# BUF_BUS_TEE_1.net
KiCad netlist of a schematic drawn in EAGLE
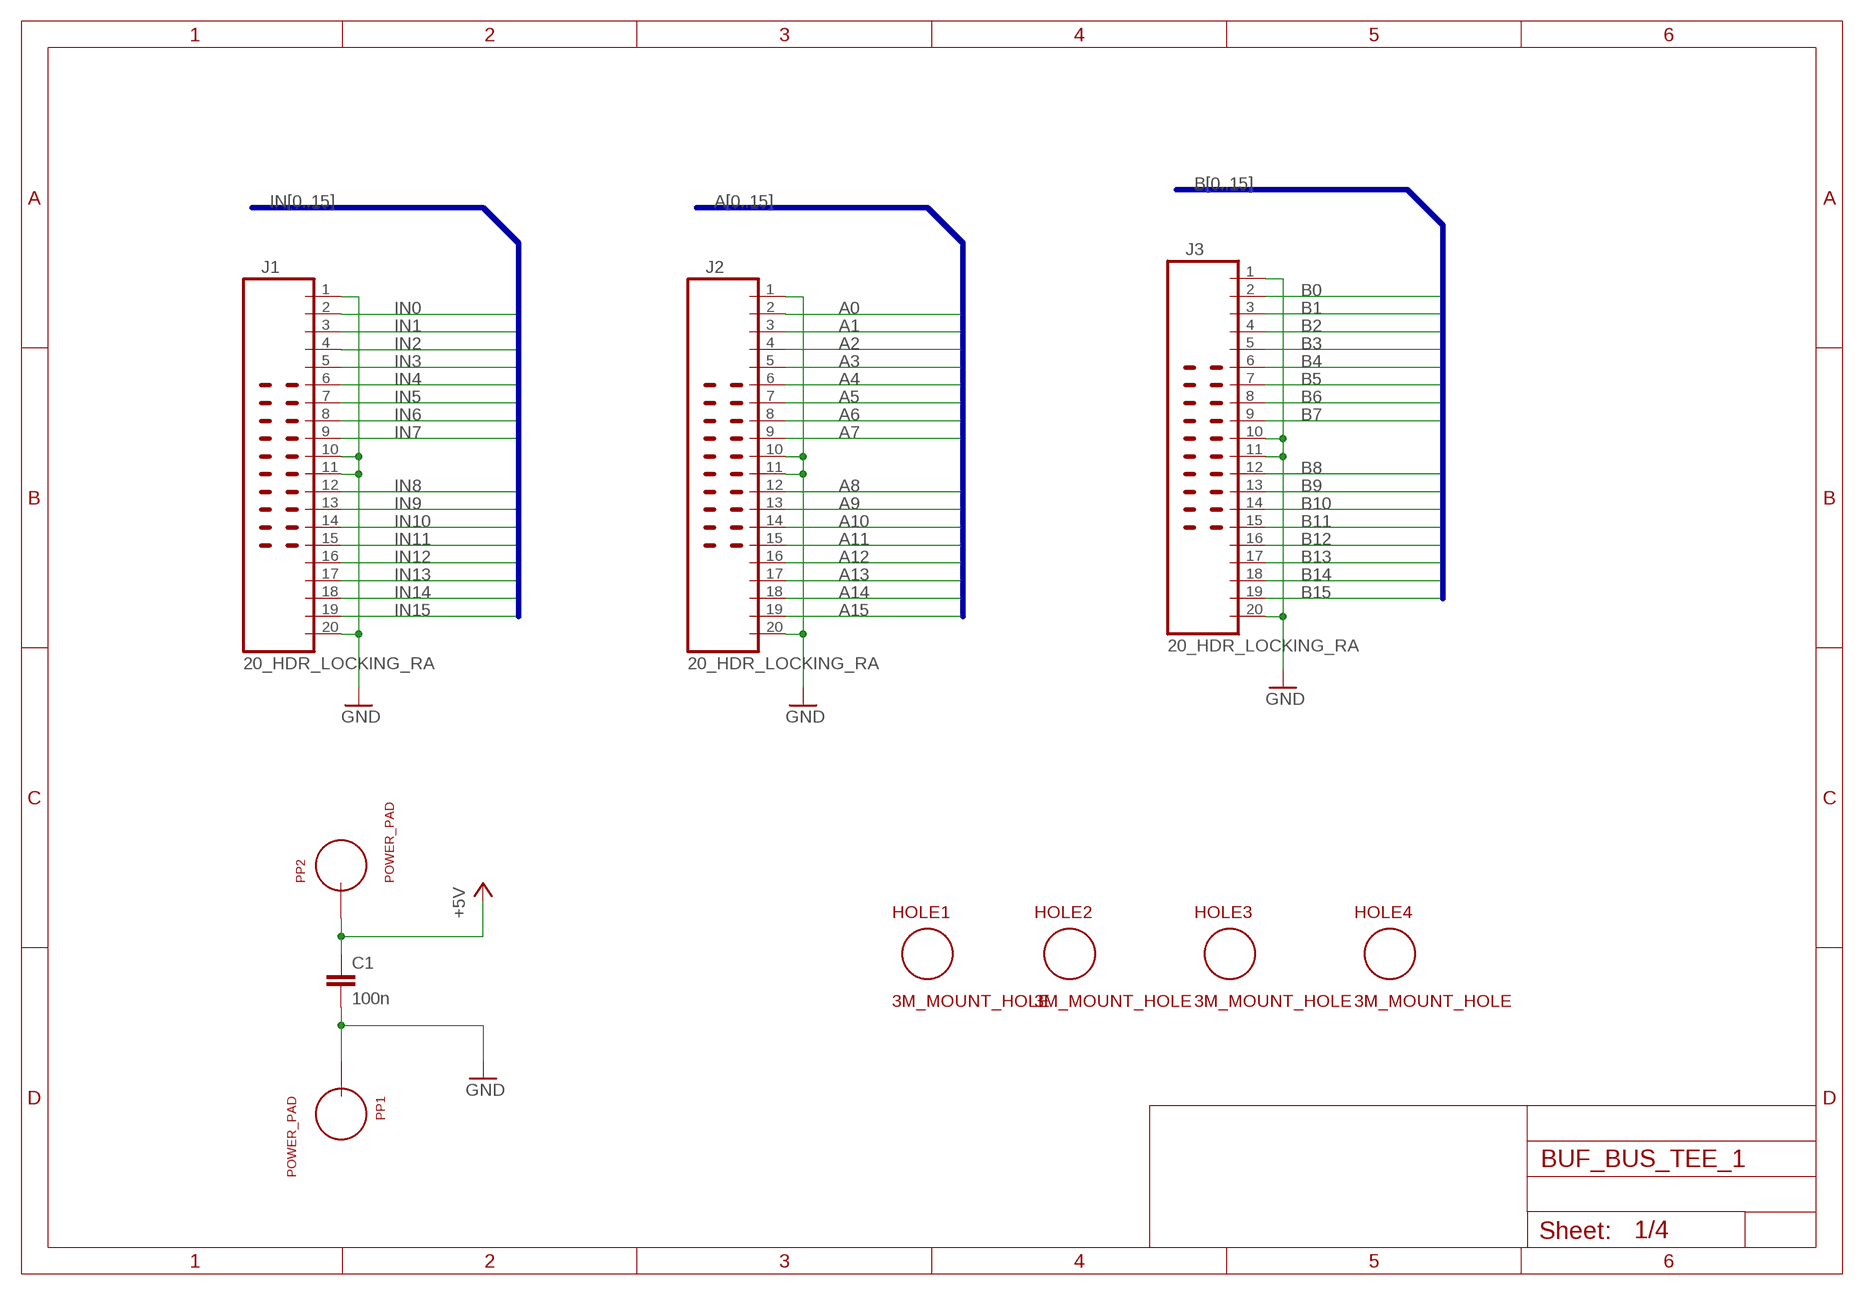
[diagram p0: schematic, sheet 1]
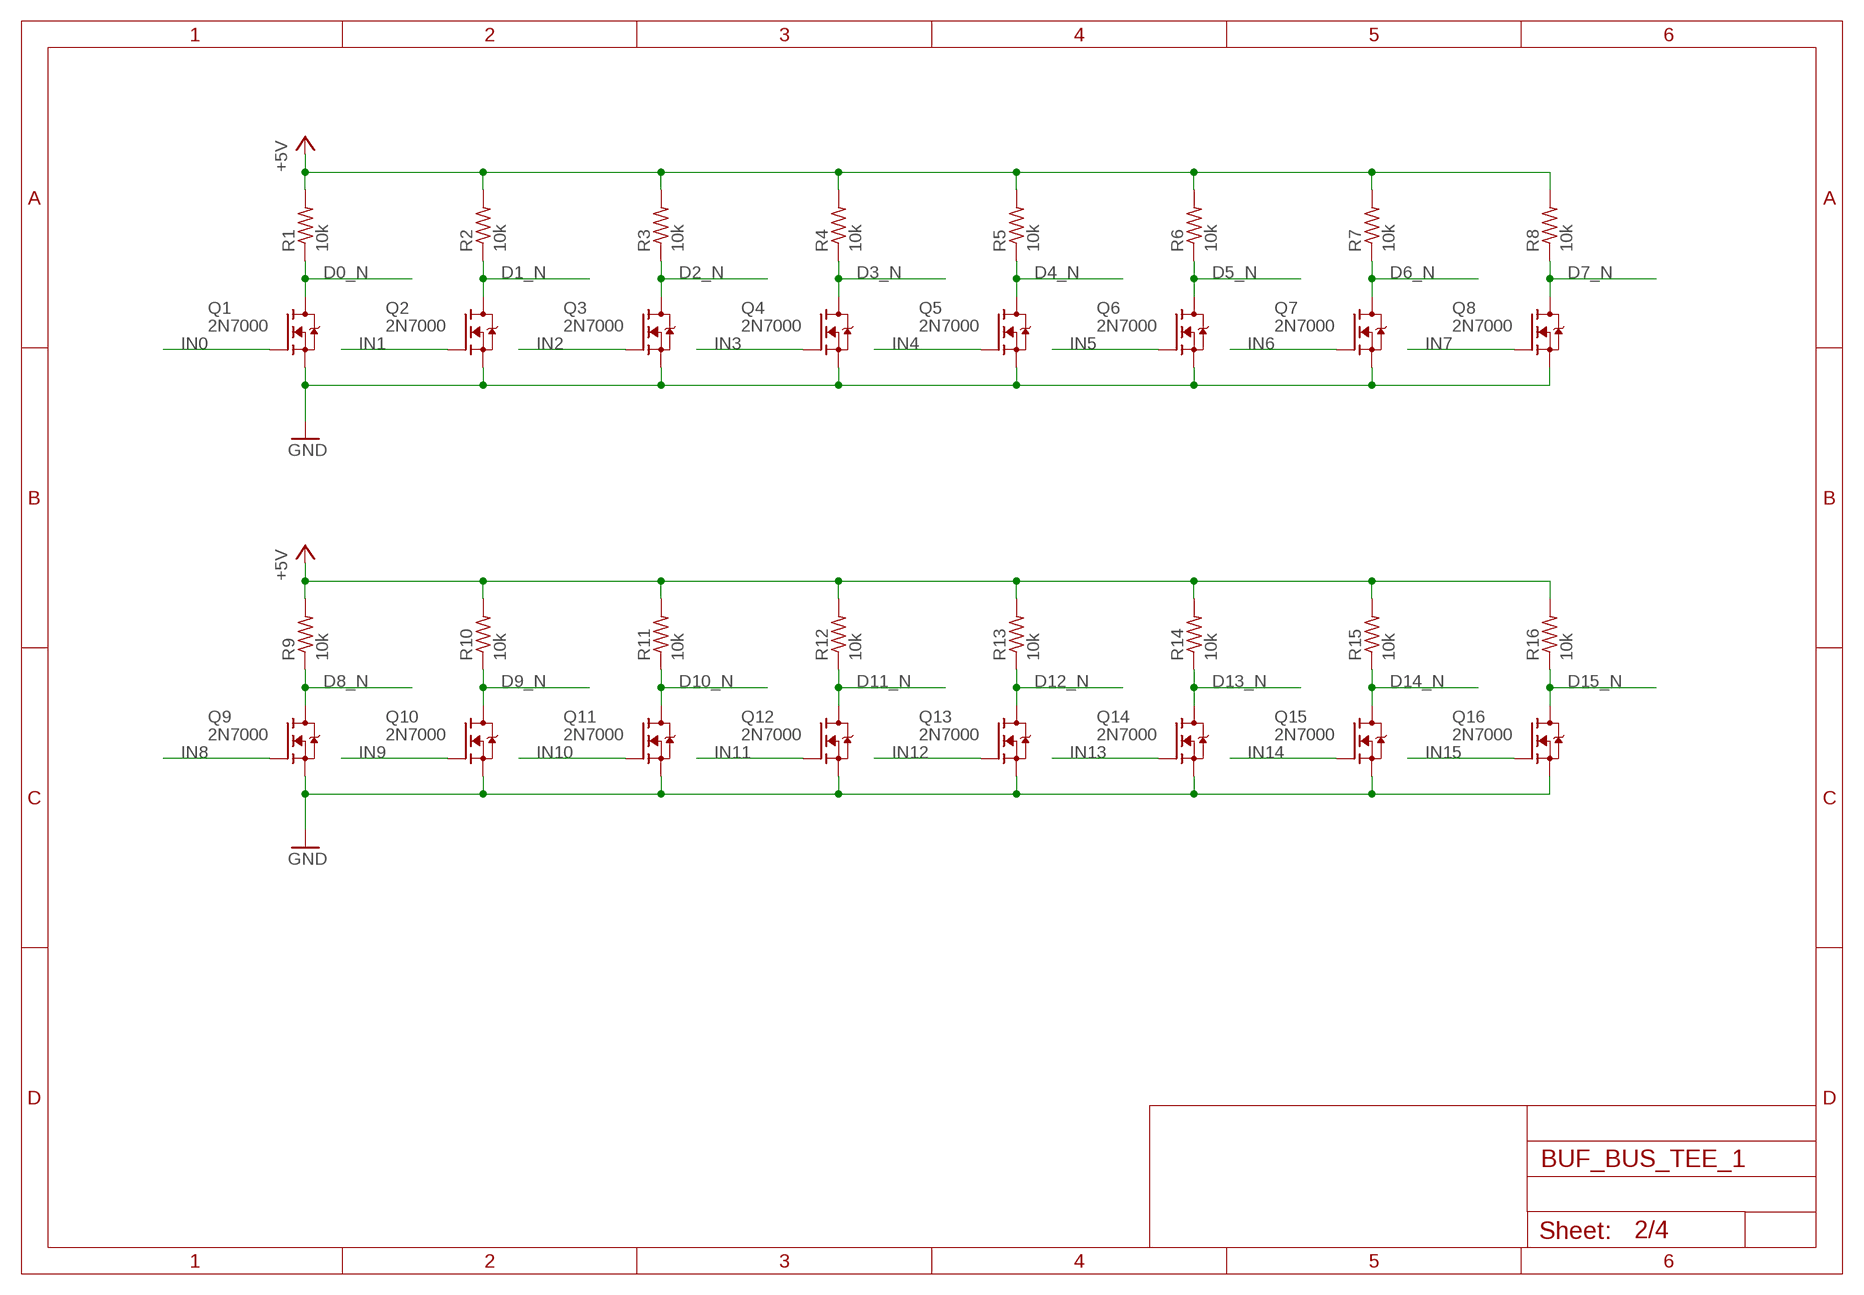
[diagram p1: schematic, sheet 2]
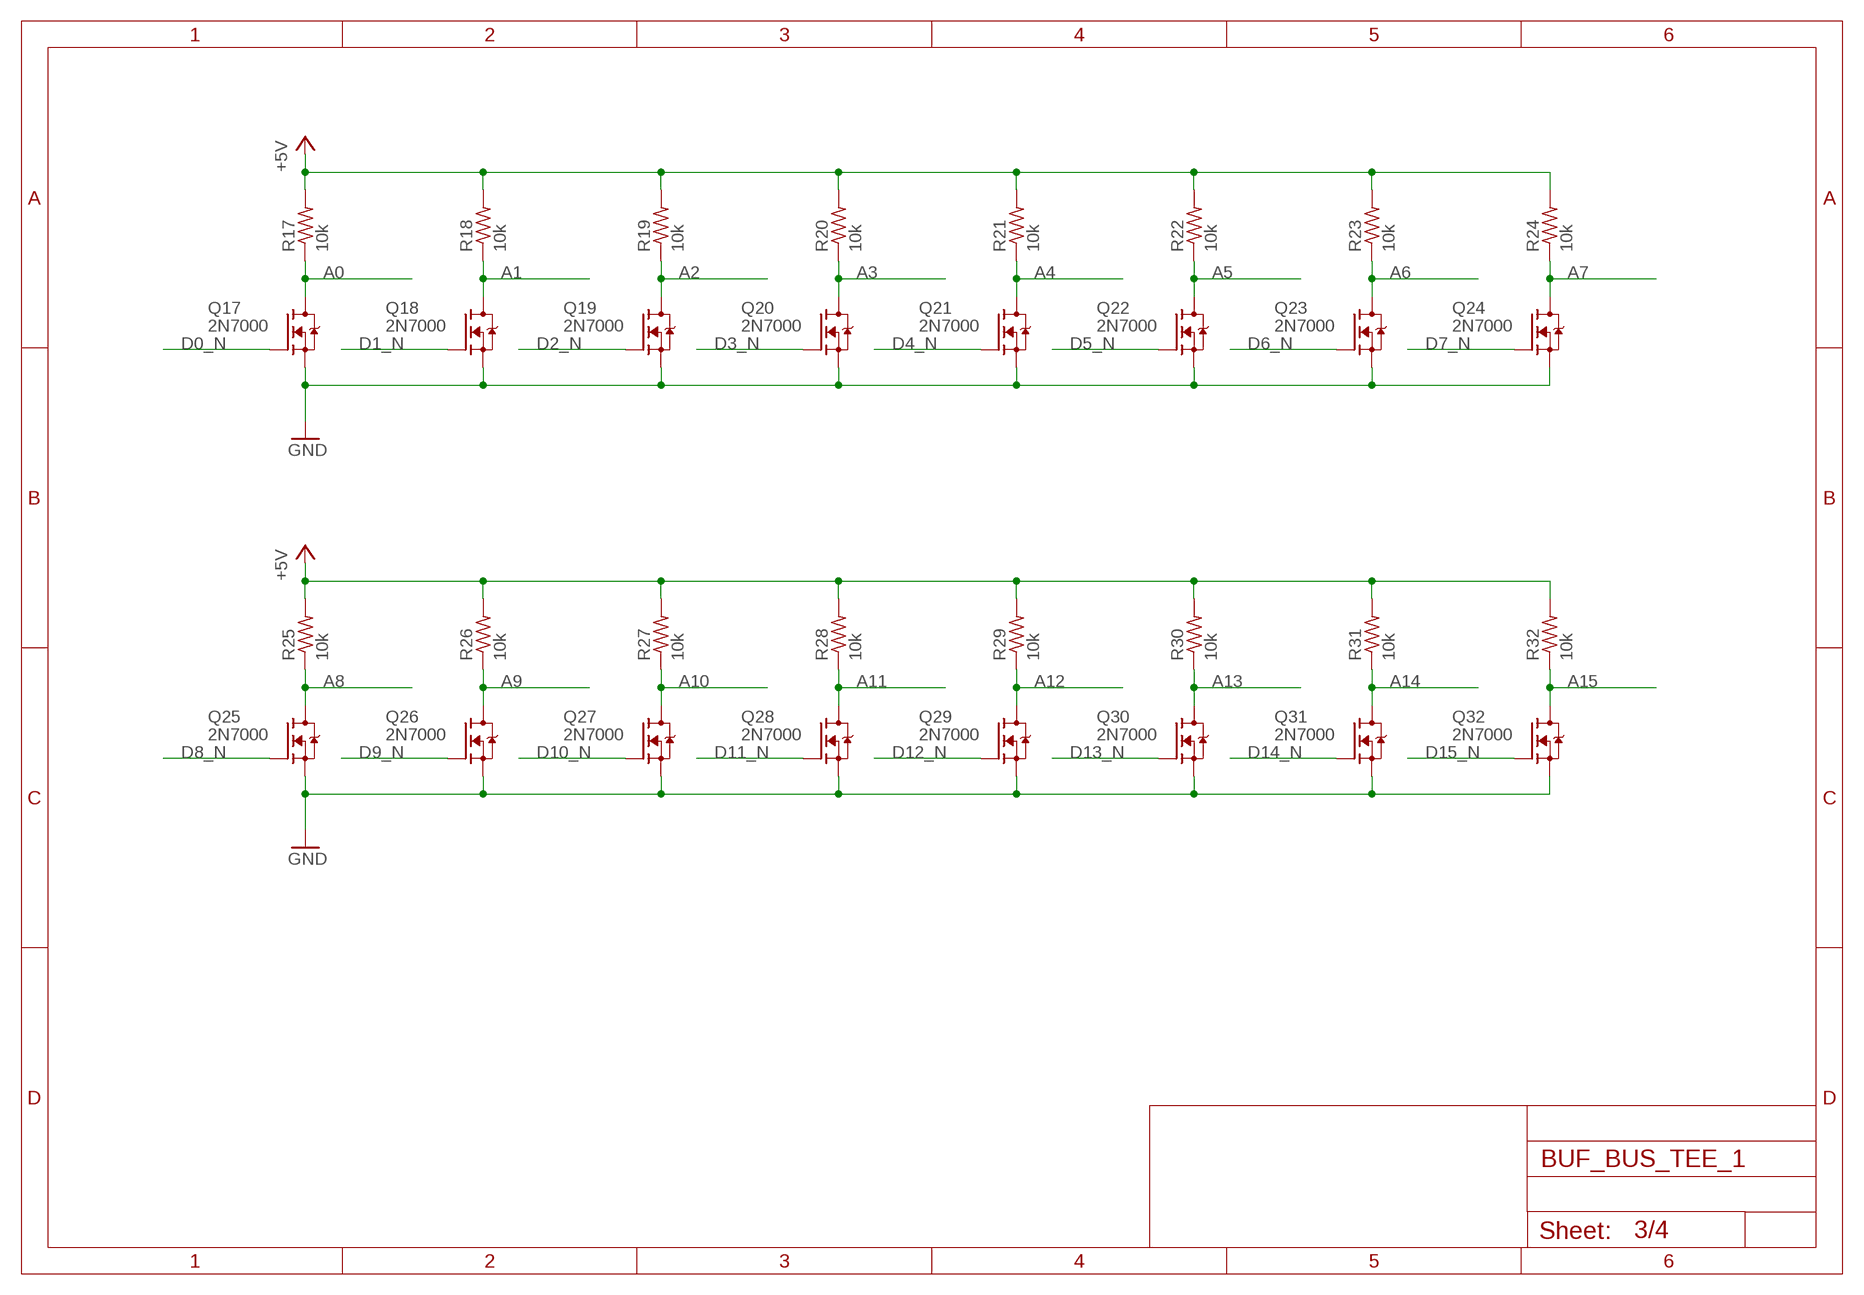
[diagram p2: schematic, sheet 3]
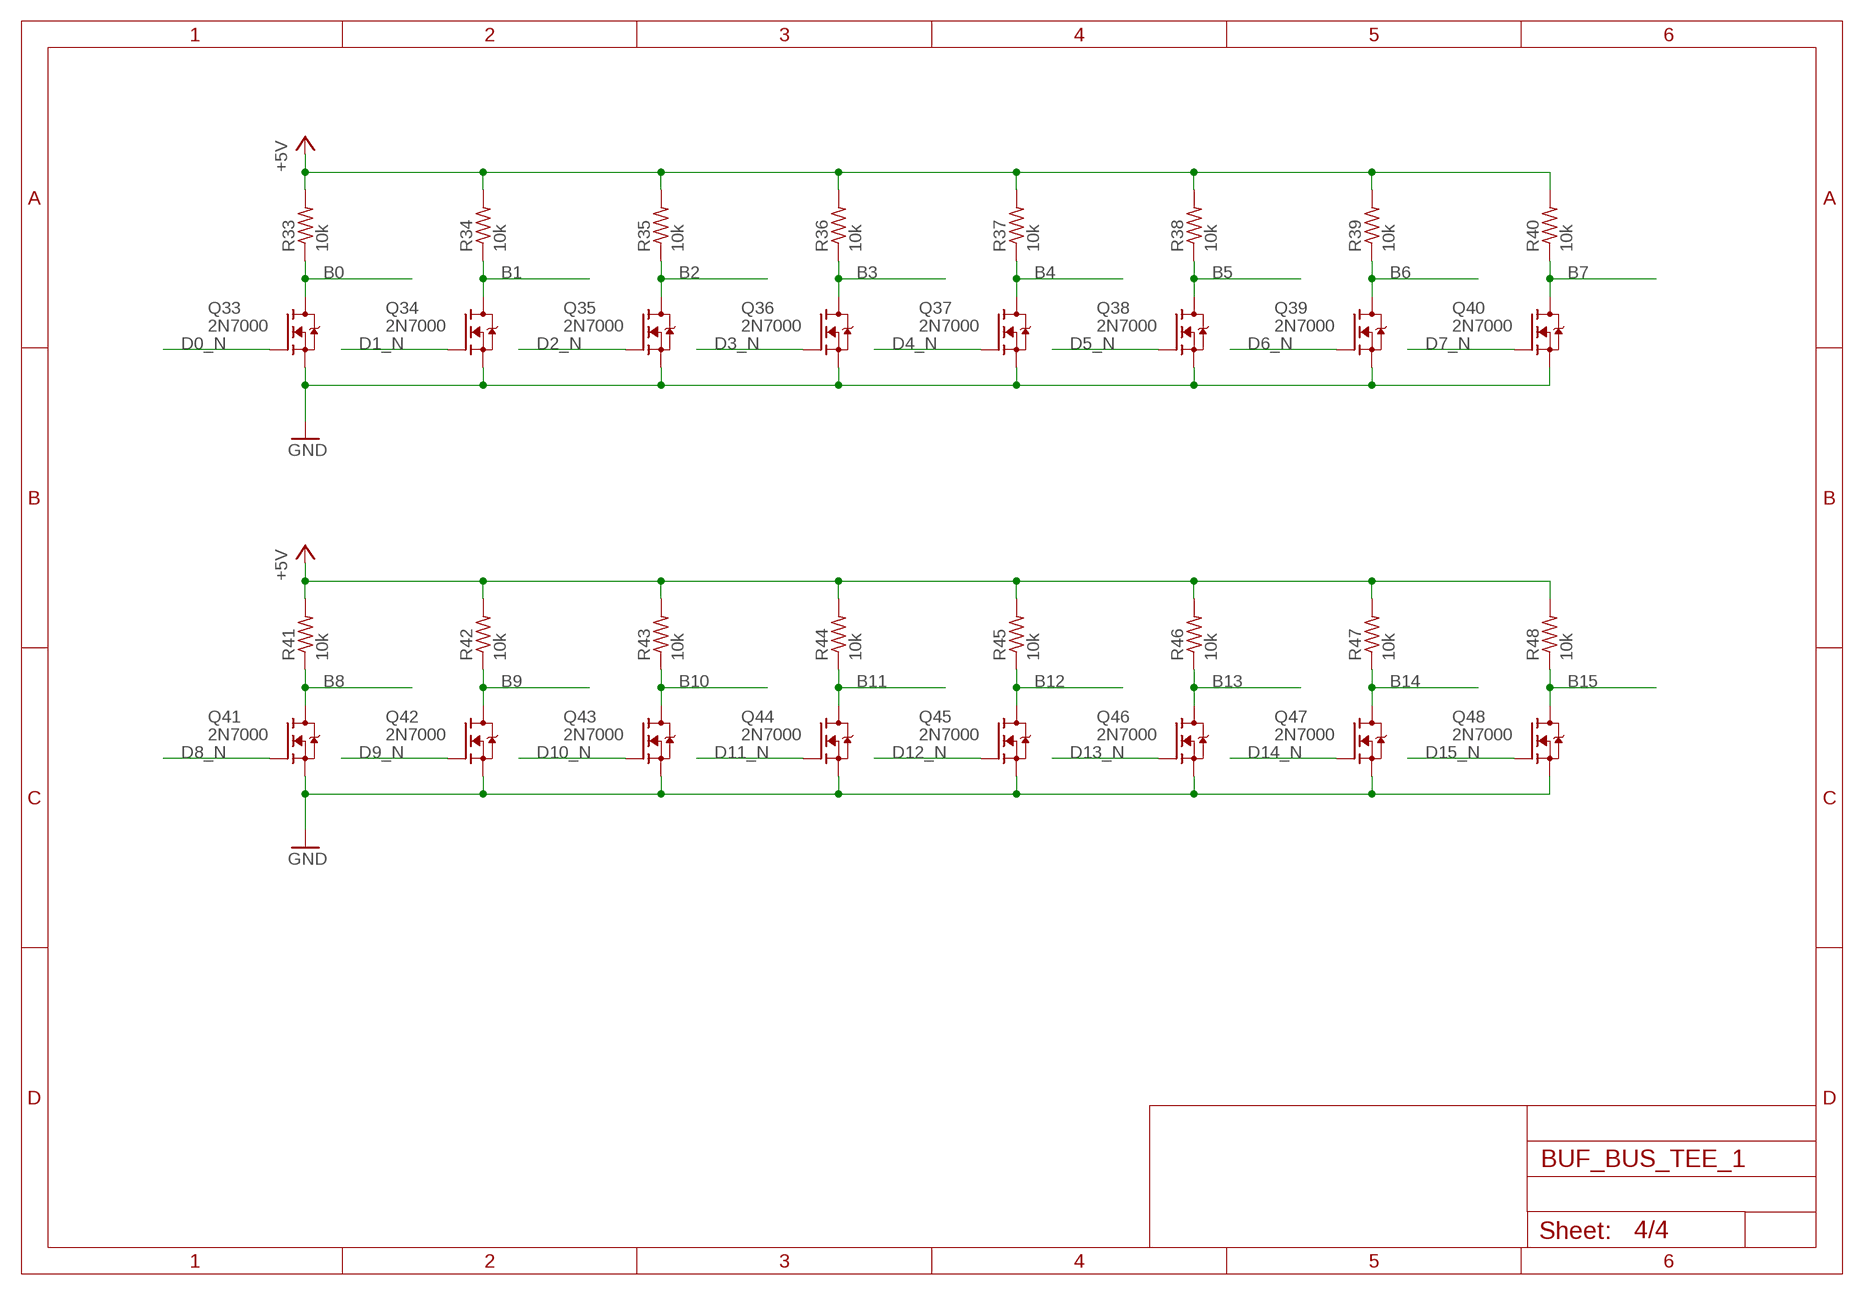
[diagram p3: schematic, sheet 4]

(export (version "E")
  (design (tool "Eeschema 10.0.6"))
  (components
    (comp (ref "Q1")
      (value "2N7000")
      (footprint "eagle-import:TO92-DGS")
      (libsource (lib "eagle-import") (part "2N7000"))
    )
    (comp (ref "Q2")
      (value "2N7000")
      (footprint "eagle-import:TO92-DGS")
      (libsource (lib "eagle-import") (part "2N7000"))
    )
    (comp (ref "Q3")
      (value "2N7000")
      (footprint "eagle-import:TO92-DGS")
      (libsource (lib "eagle-import") (part "2N7000"))
    )
    (comp (ref "Q4")
      (value "2N7000")
      (footprint "eagle-import:TO92-DGS")
      (libsource (lib "eagle-import") (part "2N7000"))
    )
    (comp (ref "Q5")
      (value "2N7000")
      (footprint "eagle-import:TO92-DGS")
      (libsource (lib "eagle-import") (part "2N7000"))
    )
    (comp (ref "Q6")
      (value "2N7000")
      (footprint "eagle-import:TO92-DGS")
      (libsource (lib "eagle-import") (part "2N7000"))
    )
    (comp (ref "Q7")
      (value "2N7000")
      (footprint "eagle-import:TO92-DGS")
      (libsource (lib "eagle-import") (part "2N7000"))
    )
    (comp (ref "Q8")
      (value "2N7000")
      (footprint "eagle-import:TO92-DGS")
      (libsource (lib "eagle-import") (part "2N7000"))
    )
    (comp (ref "Q9")
      (value "2N7000")
      (footprint "eagle-import:TO92-DGS")
      (libsource (lib "eagle-import") (part "2N7000"))
    )
    (comp (ref "Q10")
      (value "2N7000")
      (footprint "eagle-import:TO92-DGS")
      (libsource (lib "eagle-import") (part "2N7000"))
    )
    (comp (ref "Q11")
      (value "2N7000")
      (footprint "eagle-import:TO92-DGS")
      (libsource (lib "eagle-import") (part "2N7000"))
    )
    (comp (ref "Q12")
      (value "2N7000")
      (footprint "eagle-import:TO92-DGS")
      (libsource (lib "eagle-import") (part "2N7000"))
    )
    (comp (ref "Q13")
      (value "2N7000")
      (footprint "eagle-import:TO92-DGS")
      (libsource (lib "eagle-import") (part "2N7000"))
    )
    (comp (ref "Q14")
      (value "2N7000")
      (footprint "eagle-import:TO92-DGS")
      (libsource (lib "eagle-import") (part "2N7000"))
    )
    (comp (ref "Q15")
      (value "2N7000")
      (footprint "eagle-import:TO92-DGS")
      (libsource (lib "eagle-import") (part "2N7000"))
    )
    (comp (ref "Q16")
      (value "2N7000")
      (footprint "eagle-import:TO92-DGS")
      (libsource (lib "eagle-import") (part "2N7000"))
    )
    (comp (ref "R1")
      (value "10k")
      (footprint "eagle-import:R_P2INCH")
      (libsource (lib "eagle-import") (part "R_P2INCH"))
    )
    (comp (ref "R2")
      (value "10k")
      (footprint "eagle-import:R_P2INCH")
      (libsource (lib "eagle-import") (part "R_P2INCH"))
    )
    (comp (ref "R3")
      (value "10k")
      (footprint "eagle-import:R_P2INCH")
      (libsource (lib "eagle-import") (part "R_P2INCH"))
    )
    (comp (ref "R4")
      (value "10k")
      (footprint "eagle-import:R_P2INCH")
      (libsource (lib "eagle-import") (part "R_P2INCH"))
    )
    (comp (ref "R5")
      (value "10k")
      (footprint "eagle-import:R_P2INCH")
      (libsource (lib "eagle-import") (part "R_P2INCH"))
    )
    (comp (ref "R6")
      (value "10k")
      (footprint "eagle-import:R_P2INCH")
      (libsource (lib "eagle-import") (part "R_P2INCH"))
    )
    (comp (ref "R7")
      (value "10k")
      (footprint "eagle-import:R_P2INCH")
      (libsource (lib "eagle-import") (part "R_P2INCH"))
    )
    (comp (ref "R8")
      (value "10k")
      (footprint "eagle-import:R_P2INCH")
      (libsource (lib "eagle-import") (part "R_P2INCH"))
    )
    (comp (ref "R9")
      (value "10k")
      (footprint "eagle-import:R_P2INCH")
      (libsource (lib "eagle-import") (part "R_P2INCH"))
    )
    (comp (ref "R10")
      (value "10k")
      (footprint "eagle-import:R_P2INCH")
      (libsource (lib "eagle-import") (part "R_P2INCH"))
    )
    (comp (ref "R11")
      (value "10k")
      (footprint "eagle-import:R_P2INCH")
      (libsource (lib "eagle-import") (part "R_P2INCH"))
    )
    (comp (ref "R12")
      (value "10k")
      (footprint "eagle-import:R_P2INCH")
      (libsource (lib "eagle-import") (part "R_P2INCH"))
    )
    (comp (ref "R13")
      (value "10k")
      (footprint "eagle-import:R_P2INCH")
      (libsource (lib "eagle-import") (part "R_P2INCH"))
    )
    (comp (ref "R14")
      (value "10k")
      (footprint "eagle-import:R_P2INCH")
      (libsource (lib "eagle-import") (part "R_P2INCH"))
    )
    (comp (ref "R15")
      (value "10k")
      (footprint "eagle-import:R_P2INCH")
      (libsource (lib "eagle-import") (part "R_P2INCH"))
    )
    (comp (ref "R16")
      (value "10k")
      (footprint "eagle-import:R_P2INCH")
      (libsource (lib "eagle-import") (part "R_P2INCH"))
    )
    (comp (ref "C1")
      (value "100n")
      (footprint "eagle-import:CAP_P2INCH")
      (libsource (lib "eagle-import") (part "C_P2INCH"))
    )
    (comp (ref "HOLE1")
      (value "3M_MOUNT_HOLE")
      (footprint "eagle-import:3M_HOLE")
      (libsource (lib "eagle-import") (part "3M_MOUNT_HOLE"))
    )
    (comp (ref "HOLE2")
      (value "3M_MOUNT_HOLE")
      (footprint "eagle-import:3M_HOLE")
      (libsource (lib "eagle-import") (part "3M_MOUNT_HOLE"))
    )
    (comp (ref "HOLE3")
      (value "3M_MOUNT_HOLE")
      (footprint "eagle-import:3M_HOLE")
      (libsource (lib "eagle-import") (part "3M_MOUNT_HOLE"))
    )
    (comp (ref "HOLE4")
      (value "3M_MOUNT_HOLE")
      (footprint "eagle-import:3M_HOLE")
      (libsource (lib "eagle-import") (part "3M_MOUNT_HOLE"))
    )
    (comp (ref "J1")
      (value "20_HDR_LOCKING_RA")
      (footprint "eagle-import:20_HDR_LOCKING_RA")
      (libsource (lib "eagle-import") (part "20_HDR_LOCKING_RA"))
    )
    (comp (ref "J2")
      (value "20_HDR_LOCKING_RA")
      (footprint "eagle-import:20_HDR_LOCKING_RA")
      (libsource (lib "eagle-import") (part "20_HDR_LOCKING_RA"))
    )
    (comp (ref "J3")
      (value "20_HDR_LOCKING_RA")
      (footprint "eagle-import:20_HDR_LOCKING_RA")
      (libsource (lib "eagle-import") (part "20_HDR_LOCKING_RA"))
    )
    (comp (ref "PP1")
      (value "POWER_PAD")
      (footprint "eagle-import:POWER_PAD")
      (libsource (lib "eagle-import") (part "POWER_PAD"))
    )
    (comp (ref "PP2")
      (value "POWER_PAD")
      (footprint "eagle-import:POWER_PAD")
      (libsource (lib "eagle-import") (part "POWER_PAD"))
    )
    (comp (ref "Q17")
      (value "2N7000")
      (footprint "eagle-import:TO92-DGS")
      (libsource (lib "eagle-import") (part "2N7000"))
    )
    (comp (ref "Q18")
      (value "2N7000")
      (footprint "eagle-import:TO92-DGS")
      (libsource (lib "eagle-import") (part "2N7000"))
    )
    (comp (ref "Q19")
      (value "2N7000")
      (footprint "eagle-import:TO92-DGS")
      (libsource (lib "eagle-import") (part "2N7000"))
    )
    (comp (ref "Q20")
      (value "2N7000")
      (footprint "eagle-import:TO92-DGS")
      (libsource (lib "eagle-import") (part "2N7000"))
    )
    (comp (ref "Q21")
      (value "2N7000")
      (footprint "eagle-import:TO92-DGS")
      (libsource (lib "eagle-import") (part "2N7000"))
    )
    (comp (ref "Q22")
      (value "2N7000")
      (footprint "eagle-import:TO92-DGS")
      (libsource (lib "eagle-import") (part "2N7000"))
    )
    (comp (ref "Q23")
      (value "2N7000")
      (footprint "eagle-import:TO92-DGS")
      (libsource (lib "eagle-import") (part "2N7000"))
    )
    (comp (ref "Q24")
      (value "2N7000")
      (footprint "eagle-import:TO92-DGS")
      (libsource (lib "eagle-import") (part "2N7000"))
    )
    (comp (ref "Q25")
      (value "2N7000")
      (footprint "eagle-import:TO92-DGS")
      (libsource (lib "eagle-import") (part "2N7000"))
    )
    (comp (ref "Q26")
      (value "2N7000")
      (footprint "eagle-import:TO92-DGS")
      (libsource (lib "eagle-import") (part "2N7000"))
    )
    (comp (ref "Q27")
      (value "2N7000")
      (footprint "eagle-import:TO92-DGS")
      (libsource (lib "eagle-import") (part "2N7000"))
    )
    (comp (ref "Q28")
      (value "2N7000")
      (footprint "eagle-import:TO92-DGS")
      (libsource (lib "eagle-import") (part "2N7000"))
    )
    (comp (ref "Q29")
      (value "2N7000")
      (footprint "eagle-import:TO92-DGS")
      (libsource (lib "eagle-import") (part "2N7000"))
    )
    (comp (ref "Q30")
      (value "2N7000")
      (footprint "eagle-import:TO92-DGS")
      (libsource (lib "eagle-import") (part "2N7000"))
    )
    (comp (ref "Q31")
      (value "2N7000")
      (footprint "eagle-import:TO92-DGS")
      (libsource (lib "eagle-import") (part "2N7000"))
    )
    (comp (ref "Q32")
      (value "2N7000")
      (footprint "eagle-import:TO92-DGS")
      (libsource (lib "eagle-import") (part "2N7000"))
    )
    (comp (ref "R17")
      (value "10k")
      (footprint "eagle-import:R_P2INCH")
      (libsource (lib "eagle-import") (part "R_P2INCH"))
    )
    (comp (ref "R18")
      (value "10k")
      (footprint "eagle-import:R_P2INCH")
      (libsource (lib "eagle-import") (part "R_P2INCH"))
    )
    (comp (ref "R19")
      (value "10k")
      (footprint "eagle-import:R_P2INCH")
      (libsource (lib "eagle-import") (part "R_P2INCH"))
    )
    (comp (ref "R20")
      (value "10k")
      (footprint "eagle-import:R_P2INCH")
      (libsource (lib "eagle-import") (part "R_P2INCH"))
    )
    (comp (ref "R21")
      (value "10k")
      (footprint "eagle-import:R_P2INCH")
      (libsource (lib "eagle-import") (part "R_P2INCH"))
    )
    (comp (ref "R22")
      (value "10k")
      (footprint "eagle-import:R_P2INCH")
      (libsource (lib "eagle-import") (part "R_P2INCH"))
    )
    (comp (ref "R23")
      (value "10k")
      (footprint "eagle-import:R_P2INCH")
      (libsource (lib "eagle-import") (part "R_P2INCH"))
    )
    (comp (ref "R24")
      (value "10k")
      (footprint "eagle-import:R_P2INCH")
      (libsource (lib "eagle-import") (part "R_P2INCH"))
    )
    (comp (ref "R25")
      (value "10k")
      (footprint "eagle-import:R_P2INCH")
      (libsource (lib "eagle-import") (part "R_P2INCH"))
    )
    (comp (ref "R26")
      (value "10k")
      (footprint "eagle-import:R_P2INCH")
      (libsource (lib "eagle-import") (part "R_P2INCH"))
    )
    (comp (ref "R27")
      (value "10k")
      (footprint "eagle-import:R_P2INCH")
      (libsource (lib "eagle-import") (part "R_P2INCH"))
    )
    (comp (ref "R28")
      (value "10k")
      (footprint "eagle-import:R_P2INCH")
      (libsource (lib "eagle-import") (part "R_P2INCH"))
    )
    (comp (ref "R29")
      (value "10k")
      (footprint "eagle-import:R_P2INCH")
      (libsource (lib "eagle-import") (part "R_P2INCH"))
    )
    (comp (ref "R30")
      (value "10k")
      (footprint "eagle-import:R_P2INCH")
      (libsource (lib "eagle-import") (part "R_P2INCH"))
    )
    (comp (ref "R31")
      (value "10k")
      (footprint "eagle-import:R_P2INCH")
      (libsource (lib "eagle-import") (part "R_P2INCH"))
    )
    (comp (ref "R32")
      (value "10k")
      (footprint "eagle-import:R_P2INCH")
      (libsource (lib "eagle-import") (part "R_P2INCH"))
    )
    (comp (ref "Q33")
      (value "2N7000")
      (footprint "eagle-import:TO92-DGS")
      (libsource (lib "eagle-import") (part "2N7000"))
    )
    (comp (ref "Q34")
      (value "2N7000")
      (footprint "eagle-import:TO92-DGS")
      (libsource (lib "eagle-import") (part "2N7000"))
    )
    (comp (ref "Q35")
      (value "2N7000")
      (footprint "eagle-import:TO92-DGS")
      (libsource (lib "eagle-import") (part "2N7000"))
    )
    (comp (ref "Q36")
      (value "2N7000")
      (footprint "eagle-import:TO92-DGS")
      (libsource (lib "eagle-import") (part "2N7000"))
    )
    (comp (ref "Q37")
      (value "2N7000")
      (footprint "eagle-import:TO92-DGS")
      (libsource (lib "eagle-import") (part "2N7000"))
    )
    (comp (ref "Q38")
      (value "2N7000")
      (footprint "eagle-import:TO92-DGS")
      (libsource (lib "eagle-import") (part "2N7000"))
    )
    (comp (ref "Q39")
      (value "2N7000")
      (footprint "eagle-import:TO92-DGS")
      (libsource (lib "eagle-import") (part "2N7000"))
    )
    (comp (ref "Q40")
      (value "2N7000")
      (footprint "eagle-import:TO92-DGS")
      (libsource (lib "eagle-import") (part "2N7000"))
    )
    (comp (ref "Q41")
      (value "2N7000")
      (footprint "eagle-import:TO92-DGS")
      (libsource (lib "eagle-import") (part "2N7000"))
    )
    (comp (ref "Q42")
      (value "2N7000")
      (footprint "eagle-import:TO92-DGS")
      (libsource (lib "eagle-import") (part "2N7000"))
    )
    (comp (ref "Q43")
      (value "2N7000")
      (footprint "eagle-import:TO92-DGS")
      (libsource (lib "eagle-import") (part "2N7000"))
    )
    (comp (ref "Q44")
      (value "2N7000")
      (footprint "eagle-import:TO92-DGS")
      (libsource (lib "eagle-import") (part "2N7000"))
    )
    (comp (ref "Q45")
      (value "2N7000")
      (footprint "eagle-import:TO92-DGS")
      (libsource (lib "eagle-import") (part "2N7000"))
    )
    (comp (ref "Q46")
      (value "2N7000")
      (footprint "eagle-import:TO92-DGS")
      (libsource (lib "eagle-import") (part "2N7000"))
    )
    (comp (ref "Q47")
      (value "2N7000")
      (footprint "eagle-import:TO92-DGS")
      (libsource (lib "eagle-import") (part "2N7000"))
    )
    (comp (ref "Q48")
      (value "2N7000")
      (footprint "eagle-import:TO92-DGS")
      (libsource (lib "eagle-import") (part "2N7000"))
    )
    (comp (ref "R33")
      (value "10k")
      (footprint "eagle-import:R_P2INCH")
      (libsource (lib "eagle-import") (part "R_P2INCH"))
    )
    (comp (ref "R34")
      (value "10k")
      (footprint "eagle-import:R_P2INCH")
      (libsource (lib "eagle-import") (part "R_P2INCH"))
    )
    (comp (ref "R35")
      (value "10k")
      (footprint "eagle-import:R_P2INCH")
      (libsource (lib "eagle-import") (part "R_P2INCH"))
    )
    (comp (ref "R36")
      (value "10k")
      (footprint "eagle-import:R_P2INCH")
      (libsource (lib "eagle-import") (part "R_P2INCH"))
    )
    (comp (ref "R37")
      (value "10k")
      (footprint "eagle-import:R_P2INCH")
      (libsource (lib "eagle-import") (part "R_P2INCH"))
    )
    (comp (ref "R38")
      (value "10k")
      (footprint "eagle-import:R_P2INCH")
      (libsource (lib "eagle-import") (part "R_P2INCH"))
    )
    (comp (ref "R39")
      (value "10k")
      (footprint "eagle-import:R_P2INCH")
      (libsource (lib "eagle-import") (part "R_P2INCH"))
    )
    (comp (ref "R40")
      (value "10k")
      (footprint "eagle-import:R_P2INCH")
      (libsource (lib "eagle-import") (part "R_P2INCH"))
    )
    (comp (ref "R41")
      (value "10k")
      (footprint "eagle-import:R_P2INCH")
      (libsource (lib "eagle-import") (part "R_P2INCH"))
    )
    (comp (ref "R42")
      (value "10k")
      (footprint "eagle-import:R_P2INCH")
      (libsource (lib "eagle-import") (part "R_P2INCH"))
    )
    (comp (ref "R43")
      (value "10k")
      (footprint "eagle-import:R_P2INCH")
      (libsource (lib "eagle-import") (part "R_P2INCH"))
    )
    (comp (ref "R44")
      (value "10k")
      (footprint "eagle-import:R_P2INCH")
      (libsource (lib "eagle-import") (part "R_P2INCH"))
    )
    (comp (ref "R45")
      (value "10k")
      (footprint "eagle-import:R_P2INCH")
      (libsource (lib "eagle-import") (part "R_P2INCH"))
    )
    (comp (ref "R46")
      (value "10k")
      (footprint "eagle-import:R_P2INCH")
      (libsource (lib "eagle-import") (part "R_P2INCH"))
    )
    (comp (ref "R47")
      (value "10k")
      (footprint "eagle-import:R_P2INCH")
      (libsource (lib "eagle-import") (part "R_P2INCH"))
    )
    (comp (ref "R48")
      (value "10k")
      (footprint "eagle-import:R_P2INCH")
      (libsource (lib "eagle-import") (part "R_P2INCH"))
    )
  )
  (nets
    (net (code "1") (name "+5V") (class "Default")
      (node (ref "C1") (pin "1") (pinfunction "1_1") (pintype "passive"))
      (node (ref "PP2") (pin "1") (pinfunction "P$1_1") (pintype "bidirectional"))
      (node (ref "R1") (pin "2") (pinfunction "2_2") (pintype "passive"))
      (node (ref "R10") (pin "2") (pinfunction "2_2") (pintype "passive"))
      (node (ref "R11") (pin "2") (pinfunction "2_2") (pintype "passive"))
      (node (ref "R12") (pin "2") (pinfunction "2_2") (pintype "passive"))
      (node (ref "R13") (pin "2") (pinfunction "2_2") (pintype "passive"))
      (node (ref "R14") (pin "2") (pinfunction "2_2") (pintype "passive"))
      (node (ref "R15") (pin "2") (pinfunction "2_2") (pintype "passive"))
      (node (ref "R16") (pin "2") (pinfunction "2_2") (pintype "passive"))
      (node (ref "R17") (pin "2") (pinfunction "2_2") (pintype "passive"))
      (node (ref "R18") (pin "2") (pinfunction "2_2") (pintype "passive"))
      (node (ref "R19") (pin "2") (pinfunction "2_2") (pintype "passive"))
      (node (ref "R2") (pin "2") (pinfunction "2_2") (pintype "passive"))
      (node (ref "R20") (pin "2") (pinfunction "2_2") (pintype "passive"))
      (node (ref "R21") (pin "2") (pinfunction "2_2") (pintype "passive"))
      (node (ref "R22") (pin "2") (pinfunction "2_2") (pintype "passive"))
      (node (ref "R23") (pin "2") (pinfunction "2_2") (pintype "passive"))
      (node (ref "R24") (pin "2") (pinfunction "2_2") (pintype "passive"))
      (node (ref "R25") (pin "2") (pinfunction "2_2") (pintype "passive"))
      (node (ref "R26") (pin "2") (pinfunction "2_2") (pintype "passive"))
      (node (ref "R27") (pin "2") (pinfunction "2_2") (pintype "passive"))
      (node (ref "R28") (pin "2") (pinfunction "2_2") (pintype "passive"))
      (node (ref "R29") (pin "2") (pinfunction "2_2") (pintype "passive"))
      (node (ref "R3") (pin "2") (pinfunction "2_2") (pintype "passive"))
      (node (ref "R30") (pin "2") (pinfunction "2_2") (pintype "passive"))
      (node (ref "R31") (pin "2") (pinfunction "2_2") (pintype "passive"))
      (node (ref "R32") (pin "2") (pinfunction "2_2") (pintype "passive"))
      (node (ref "R33") (pin "2") (pinfunction "2_2") (pintype "passive"))
      (node (ref "R34") (pin "2") (pinfunction "2_2") (pintype "passive"))
      (node (ref "R35") (pin "2") (pinfunction "2_2") (pintype "passive"))
      (node (ref "R36") (pin "2") (pinfunction "2_2") (pintype "passive"))
      (node (ref "R37") (pin "2") (pinfunction "2_2") (pintype "passive"))
      (node (ref "R38") (pin "2") (pinfunction "2_2") (pintype "passive"))
      (node (ref "R39") (pin "2") (pinfunction "2_2") (pintype "passive"))
      (node (ref "R4") (pin "2") (pinfunction "2_2") (pintype "passive"))
      (node (ref "R40") (pin "2") (pinfunction "2_2") (pintype "passive"))
      (node (ref "R41") (pin "2") (pinfunction "2_2") (pintype "passive"))
      (node (ref "R42") (pin "2") (pinfunction "2_2") (pintype "passive"))
      (node (ref "R43") (pin "2") (pinfunction "2_2") (pintype "passive"))
      (node (ref "R44") (pin "2") (pinfunction "2_2") (pintype "passive"))
      (node (ref "R45") (pin "2") (pinfunction "2_2") (pintype "passive"))
      (node (ref "R46") (pin "2") (pinfunction "2_2") (pintype "passive"))
      (node (ref "R47") (pin "2") (pinfunction "2_2") (pintype "passive"))
      (node (ref "R48") (pin "2") (pinfunction "2_2") (pintype "passive"))
      (node (ref "R5") (pin "2") (pinfunction "2_2") (pintype "passive"))
      (node (ref "R6") (pin "2") (pinfunction "2_2") (pintype "passive"))
      (node (ref "R7") (pin "2") (pinfunction "2_2") (pintype "passive"))
      (node (ref "R8") (pin "2") (pinfunction "2_2") (pintype "passive"))
      (node (ref "R9") (pin "2") (pinfunction "2_2") (pintype "passive"))
    )
    (net (code "5") (name "A0") (class "Default")
      (node (ref "J2") (pin "2") (pinfunction "2_2") (pintype "bidirectional"))
      (node (ref "Q17") (pin "D") (pinfunction "D_D") (pintype "passive"))
      (node (ref "R17") (pin "1") (pinfunction "1_1") (pintype "passive"))
    )
    (net (code "6") (name "A1") (class "Default")
      (node (ref "J2") (pin "3") (pinfunction "3_3") (pintype "bidirectional"))
      (node (ref "Q18") (pin "D") (pinfunction "D_D") (pintype "passive"))
      (node (ref "R18") (pin "1") (pinfunction "1_1") (pintype "passive"))
    )
    (net (code "7") (name "A2") (class "Default")
      (node (ref "J2") (pin "4") (pinfunction "4_4") (pintype "bidirectional"))
      (node (ref "Q19") (pin "D") (pinfunction "D_D") (pintype "passive"))
      (node (ref "R19") (pin "1") (pinfunction "1_1") (pintype "passive"))
    )
    (net (code "8") (name "A3") (class "Default")
      (node (ref "J2") (pin "5") (pinfunction "5_5") (pintype "bidirectional"))
      (node (ref "Q20") (pin "D") (pinfunction "D_D") (pintype "passive"))
      (node (ref "R20") (pin "1") (pinfunction "1_1") (pintype "passive"))
    )
    (net (code "9") (name "A4") (class "Default")
      (node (ref "J2") (pin "6") (pinfunction "6_6") (pintype "bidirectional"))
      (node (ref "Q21") (pin "D") (pinfunction "D_D") (pintype "passive"))
      (node (ref "R21") (pin "1") (pinfunction "1_1") (pintype "passive"))
    )
    (net (code "10") (name "A5") (class "Default")
      (node (ref "J2") (pin "7") (pinfunction "7_7") (pintype "bidirectional"))
      (node (ref "Q22") (pin "D") (pinfunction "D_D") (pintype "passive"))
      (node (ref "R22") (pin "1") (pinfunction "1_1") (pintype "passive"))
    )
    (net (code "11") (name "A6") (class "Default")
      (node (ref "J2") (pin "8") (pinfunction "8_8") (pintype "bidirectional"))
      (node (ref "Q23") (pin "D") (pinfunction "D_D") (pintype "passive"))
      (node (ref "R23") (pin "1") (pinfunction "1_1") (pintype "passive"))
    )
    (net (code "12") (name "A7") (class "Default")
      (node (ref "J2") (pin "9") (pinfunction "9_9") (pintype "bidirectional"))
      (node (ref "Q24") (pin "D") (pinfunction "D_D") (pintype "passive"))
      (node (ref "R24") (pin "1") (pinfunction "1_1") (pintype "passive"))
    )
    (net (code "13") (name "A8") (class "Default")
      (node (ref "J2") (pin "12") (pinfunction "12_12") (pintype "bidirectional"))
      (node (ref "Q25") (pin "D") (pinfunction "D_D") (pintype "passive"))
      (node (ref "R25") (pin "1") (pinfunction "1_1") (pintype "passive"))
    )
    (net (code "14") (name "A9") (class "Default")
      (node (ref "J2") (pin "13") (pinfunction "13_13") (pintype "bidirectional"))
      (node (ref "Q26") (pin "D") (pinfunction "D_D") (pintype "passive"))
      (node (ref "R26") (pin "1") (pinfunction "1_1") (pintype "passive"))
    )
    (net (code "15") (name "A10") (class "Default")
      (node (ref "J2") (pin "14") (pinfunction "14_14") (pintype "bidirectional"))
      (node (ref "Q27") (pin "D") (pinfunction "D_D") (pintype "passive"))
      (node (ref "R27") (pin "1") (pinfunction "1_1") (pintype "passive"))
    )
    (net (code "16") (name "A11") (class "Default")
      (node (ref "J2") (pin "15") (pinfunction "15_15") (pintype "bidirectional"))
      (node (ref "Q28") (pin "D") (pinfunction "D_D") (pintype "passive"))
      (node (ref "R28") (pin "1") (pinfunction "1_1") (pintype "passive"))
    )
    (net (code "17") (name "A12") (class "Default")
      (node (ref "J2") (pin "16") (pinfunction "16_16") (pintype "bidirectional"))
      (node (ref "Q29") (pin "D") (pinfunction "D_D") (pintype "passive"))
      (node (ref "R29") (pin "1") (pinfunction "1_1") (pintype "passive"))
    )
    (net (code "18") (name "A13") (class "Default")
      (node (ref "J2") (pin "17") (pinfunction "17_17") (pintype "bidirectional"))
      (node (ref "Q30") (pin "D") (pinfunction "D_D") (pintype "passive"))
      (node (ref "R30") (pin "1") (pinfunction "1_1") (pintype "passive"))
    )
    (net (code "19") (name "A14") (class "Default")
      (node (ref "J2") (pin "18") (pinfunction "18_18") (pintype "bidirectional"))
      (node (ref "Q31") (pin "D") (pinfunction "D_D") (pintype "passive"))
      (node (ref "R31") (pin "1") (pinfunction "1_1") (pintype "passive"))
    )
    (net (code "20") (name "A15") (class "Default")
      (node (ref "J2") (pin "19") (pinfunction "19_19") (pintype "bidirectional"))
      (node (ref "Q32") (pin "D") (pinfunction "D_D") (pintype "passive"))
      (node (ref "R32") (pin "1") (pinfunction "1_1") (pintype "passive"))
    )
    (net (code "21") (name "B0") (class "Default")
      (node (ref "J3") (pin "2") (pinfunction "2_2") (pintype "bidirectional"))
      (node (ref "Q33") (pin "D") (pinfunction "D_D") (pintype "passive"))
      (node (ref "R33") (pin "1") (pinfunction "1_1") (pintype "passive"))
    )
    (net (code "22") (name "B1") (class "Default")
      (node (ref "J3") (pin "3") (pinfunction "3_3") (pintype "bidirectional"))
      (node (ref "Q34") (pin "D") (pinfunction "D_D") (pintype "passive"))
      (node (ref "R34") (pin "1") (pinfunction "1_1") (pintype "passive"))
    )
    (net (code "23") (name "B2") (class "Default")
      (node (ref "J3") (pin "4") (pinfunction "4_4") (pintype "bidirectional"))
      (node (ref "Q35") (pin "D") (pinfunction "D_D") (pintype "passive"))
      (node (ref "R35") (pin "1") (pinfunction "1_1") (pintype "passive"))
    )
    (net (code "24") (name "B3") (class "Default")
      (node (ref "J3") (pin "5") (pinfunction "5_5") (pintype "bidirectional"))
      (node (ref "Q36") (pin "D") (pinfunction "D_D") (pintype "passive"))
      (node (ref "R36") (pin "1") (pinfunction "1_1") (pintype "passive"))
    )
    (net (code "25") (name "B4") (class "Default")
      (node (ref "J3") (pin "6") (pinfunction "6_6") (pintype "bidirectional"))
      (node (ref "Q37") (pin "D") (pinfunction "D_D") (pintype "passive"))
      (node (ref "R37") (pin "1") (pinfunction "1_1") (pintype "passive"))
    )
    (net (code "26") (name "B5") (class "Default")
      (node (ref "J3") (pin "7") (pinfunction "7_7") (pintype "bidirectional"))
      (node (ref "Q38") (pin "D") (pinfunction "D_D") (pintype "passive"))
      (node (ref "R38") (pin "1") (pinfunction "1_1") (pintype "passive"))
    )
    (net (code "27") (name "B6") (class "Default")
      (node (ref "J3") (pin "8") (pinfunction "8_8") (pintype "bidirectional"))
      (node (ref "Q39") (pin "D") (pinfunction "D_D") (pintype "passive"))
      (node (ref "R39") (pin "1") (pinfunction "1_1") (pintype "passive"))
    )
    (net (code "28") (name "B7") (class "Default")
      (node (ref "J3") (pin "9") (pinfunction "9_9") (pintype "bidirectional"))
      (node (ref "Q40") (pin "D") (pinfunction "D_D") (pintype "passive"))
      (node (ref "R40") (pin "1") (pinfunction "1_1") (pintype "passive"))
    )
    (net (code "29") (name "B8") (class "Default")
      (node (ref "J3") (pin "12") (pinfunction "12_12") (pintype "bidirectional"))
      (node (ref "Q41") (pin "D") (pinfunction "D_D") (pintype "passive"))
      (node (ref "R41") (pin "1") (pinfunction "1_1") (pintype "passive"))
    )
    (net (code "30") (name "B9") (class "Default")
      (node (ref "J3") (pin "13") (pinfunction "13_13") (pintype "bidirectional"))
      (node (ref "Q42") (pin "D") (pinfunction "D_D") (pintype "passive"))
      (node (ref "R42") (pin "1") (pinfunction "1_1") (pintype "passive"))
    )
    (net (code "31") (name "B10") (class "Default")
      (node (ref "J3") (pin "14") (pinfunction "14_14") (pintype "bidirectional"))
      (node (ref "Q43") (pin "D") (pinfunction "D_D") (pintype "passive"))
      (node (ref "R43") (pin "1") (pinfunction "1_1") (pintype "passive"))
    )
    (net (code "32") (name "B11") (class "Default")
      (node (ref "J3") (pin "15") (pinfunction "15_15") (pintype "bidirectional"))
      (node (ref "Q44") (pin "D") (pinfunction "D_D") (pintype "passive"))
      (node (ref "R44") (pin "1") (pinfunction "1_1") (pintype "passive"))
    )
    (net (code "33") (name "B12") (class "Default")
      (node (ref "J3") (pin "16") (pinfunction "16_16") (pintype "bidirectional"))
      (node (ref "Q45") (pin "D") (pinfunction "D_D") (pintype "passive"))
      (node (ref "R45") (pin "1") (pinfunction "1_1") (pintype "passive"))
    )
    (net (code "34") (name "B13") (class "Default")
      (node (ref "J3") (pin "17") (pinfunction "17_17") (pintype "bidirectional"))
      (node (ref "Q46") (pin "D") (pinfunction "D_D") (pintype "passive"))
      (node (ref "R46") (pin "1") (pinfunction "1_1") (pintype "passive"))
    )
    (net (code "35") (name "B14") (class "Default")
      (node (ref "J3") (pin "18") (pinfunction "18_18") (pintype "bidirectional"))
      (node (ref "Q47") (pin "D") (pinfunction "D_D") (pintype "passive"))
      (node (ref "R47") (pin "1") (pinfunction "1_1") (pintype "passive"))
    )
    (net (code "36") (name "B15") (class "Default")
      (node (ref "J3") (pin "19") (pinfunction "19_19") (pintype "bidirectional"))
      (node (ref "Q48") (pin "D") (pinfunction "D_D") (pintype "passive"))
      (node (ref "R48") (pin "1") (pinfunction "1_1") (pintype "passive"))
    )
    (net (code "37") (name "D0_N") (class "Default")
      (node (ref "Q1") (pin "D") (pinfunction "D_D") (pintype "passive"))
      (node (ref "Q17") (pin "G") (pinfunction "G_G") (pintype "passive"))
      (node (ref "Q33") (pin "G") (pinfunction "G_G") (pintype "passive"))
      (node (ref "R1") (pin "1") (pinfunction "1_1") (pintype "passive"))
    )
    (net (code "38") (name "D1_N") (class "Default")
      (node (ref "Q18") (pin "G") (pinfunction "G_G") (pintype "passive"))
      (node (ref "Q2") (pin "D") (pinfunction "D_D") (pintype "passive"))
      (node (ref "Q34") (pin "G") (pinfunction "G_G") (pintype "passive"))
      (node (ref "R2") (pin "1") (pinfunction "1_1") (pintype "passive"))
    )
    (net (code "39") (name "D2_N") (class "Default")
      (node (ref "Q19") (pin "G") (pinfunction "G_G") (pintype "passive"))
      (node (ref "Q3") (pin "D") (pinfunction "D_D") (pintype "passive"))
      (node (ref "Q35") (pin "G") (pinfunction "G_G") (pintype "passive"))
      (node (ref "R3") (pin "1") (pinfunction "1_1") (pintype "passive"))
    )
    (net (code "40") (name "D3_N") (class "Default")
      (node (ref "Q20") (pin "G") (pinfunction "G_G") (pintype "passive"))
      (node (ref "Q36") (pin "G") (pinfunction "G_G") (pintype "passive"))
      (node (ref "Q4") (pin "D") (pinfunction "D_D") (pintype "passive"))
      (node (ref "R4") (pin "1") (pinfunction "1_1") (pintype "passive"))
    )
    (net (code "41") (name "D4_N") (class "Default")
      (node (ref "Q21") (pin "G") (pinfunction "G_G") (pintype "passive"))
      (node (ref "Q37") (pin "G") (pinfunction "G_G") (pintype "passive"))
      (node (ref "Q5") (pin "D") (pinfunction "D_D") (pintype "passive"))
      (node (ref "R5") (pin "1") (pinfunction "1_1") (pintype "passive"))
    )
    (net (code "42") (name "D5_N") (class "Default")
      (node (ref "Q22") (pin "G") (pinfunction "G_G") (pintype "passive"))
      (node (ref "Q38") (pin "G") (pinfunction "G_G") (pintype "passive"))
      (node (ref "Q6") (pin "D") (pinfunction "D_D") (pintype "passive"))
      (node (ref "R6") (pin "1") (pinfunction "1_1") (pintype "passive"))
    )
    (net (code "43") (name "D6_N") (class "Default")
      (node (ref "Q23") (pin "G") (pinfunction "G_G") (pintype "passive"))
      (node (ref "Q39") (pin "G") (pinfunction "G_G") (pintype "passive"))
      (node (ref "Q7") (pin "D") (pinfunction "D_D") (pintype "passive"))
      (node (ref "R7") (pin "1") (pinfunction "1_1") (pintype "passive"))
    )
    (net (code "44") (name "D7_N") (class "Default")
      (node (ref "Q24") (pin "G") (pinfunction "G_G") (pintype "passive"))
      (node (ref "Q40") (pin "G") (pinfunction "G_G") (pintype "passive"))
      (node (ref "Q8") (pin "D") (pinfunction "D_D") (pintype "passive"))
      (node (ref "R8") (pin "1") (pinfunction "1_1") (pintype "passive"))
    )
    (net (code "45") (name "D8_N") (class "Default")
      (node (ref "Q25") (pin "G") (pinfunction "G_G") (pintype "passive"))
      (node (ref "Q41") (pin "G") (pinfunction "G_G") (pintype "passive"))
      (node (ref "Q9") (pin "D") (pinfunction "D_D") (pintype "passive"))
      (node (ref "R9") (pin "1") (pinfunction "1_1") (pintype "passive"))
    )
    (net (code "46") (name "D9_N") (class "Default")
      (node (ref "Q10") (pin "D") (pinfunction "D_D") (pintype "passive"))
      (node (ref "Q26") (pin "G") (pinfunction "G_G") (pintype "passive"))
      (node (ref "Q42") (pin "G") (pinfunction "G_G") (pintype "passive"))
      (node (ref "R10") (pin "1") (pinfunction "1_1") (pintype "passive"))
    )
    (net (code "47") (name "D10_N") (class "Default")
      (node (ref "Q11") (pin "D") (pinfunction "D_D") (pintype "passive"))
      (node (ref "Q27") (pin "G") (pinfunction "G_G") (pintype "passive"))
      (node (ref "Q43") (pin "G") (pinfunction "G_G") (pintype "passive"))
      (node (ref "R11") (pin "1") (pinfunction "1_1") (pintype "passive"))
    )
    (net (code "48") (name "D11_N") (class "Default")
      (node (ref "Q12") (pin "D") (pinfunction "D_D") (pintype "passive"))
      (node (ref "Q28") (pin "G") (pinfunction "G_G") (pintype "passive"))
      (node (ref "Q44") (pin "G") (pinfunction "G_G") (pintype "passive"))
      (node (ref "R12") (pin "1") (pinfunction "1_1") (pintype "passive"))
    )
    (net (code "49") (name "D12_N") (class "Default")
      (node (ref "Q13") (pin "D") (pinfunction "D_D") (pintype "passive"))
      (node (ref "Q29") (pin "G") (pinfunction "G_G") (pintype "passive"))
      (node (ref "Q45") (pin "G") (pinfunction "G_G") (pintype "passive"))
      (node (ref "R13") (pin "1") (pinfunction "1_1") (pintype "passive"))
    )
    (net (code "50") (name "D13_N") (class "Default")
      (node (ref "Q14") (pin "D") (pinfunction "D_D") (pintype "passive"))
      (node (ref "Q30") (pin "G") (pinfunction "G_G") (pintype "passive"))
      (node (ref "Q46") (pin "G") (pinfunction "G_G") (pintype "passive"))
      (node (ref "R14") (pin "1") (pinfunction "1_1") (pintype "passive"))
    )
    (net (code "51") (name "D14_N") (class "Default")
      (node (ref "Q15") (pin "D") (pinfunction "D_D") (pintype "passive"))
      (node (ref "Q31") (pin "G") (pinfunction "G_G") (pintype "passive"))
      (node (ref "Q47") (pin "G") (pinfunction "G_G") (pintype "passive"))
      (node (ref "R15") (pin "1") (pinfunction "1_1") (pintype "passive"))
    )
    (net (code "52") (name "D15_N") (class "Default")
      (node (ref "Q16") (pin "D") (pinfunction "D_D") (pintype "passive"))
      (node (ref "Q32") (pin "G") (pinfunction "G_G") (pintype "passive"))
      (node (ref "Q48") (pin "G") (pinfunction "G_G") (pintype "passive"))
      (node (ref "R16") (pin "1") (pinfunction "1_1") (pintype "passive"))
    )
    (net (code "53") (name "GND") (class "Default")
      (node (ref "C1") (pin "2") (pinfunction "2_2") (pintype "passive"))
      (node (ref "J1") (pin "1") (pinfunction "1_1") (pintype "bidirectional"))
      (node (ref "J1") (pin "10") (pinfunction "10_10") (pintype "bidirectional"))
      (node (ref "J1") (pin "11") (pinfunction "11_11") (pintype "bidirectional"))
      (node (ref "J1") (pin "20") (pinfunction "20_20") (pintype "bidirectional"))
      (node (ref "J2") (pin "1") (pinfunction "1_1") (pintype "bidirectional"))
      (node (ref "J2") (pin "10") (pinfunction "10_10") (pintype "bidirectional"))
      (node (ref "J2") (pin "11") (pinfunction "11_11") (pintype "bidirectional"))
      (node (ref "J2") (pin "20") (pinfunction "20_20") (pintype "bidirectional"))
      (node (ref "J3") (pin "1") (pinfunction "1_1") (pintype "bidirectional"))
      (node (ref "J3") (pin "10") (pinfunction "10_10") (pintype "bidirectional"))
      (node (ref "J3") (pin "11") (pinfunction "11_11") (pintype "bidirectional"))
      (node (ref "J3") (pin "20") (pinfunction "20_20") (pintype "bidirectional"))
      (node (ref "PP1") (pin "1") (pinfunction "P$1_1") (pintype "bidirectional"))
      (node (ref "Q1") (pin "S") (pinfunction "S_S") (pintype "passive"))
      (node (ref "Q10") (pin "S") (pinfunction "S_S") (pintype "passive"))
      (node (ref "Q11") (pin "S") (pinfunction "S_S") (pintype "passive"))
      (node (ref "Q12") (pin "S") (pinfunction "S_S") (pintype "passive"))
      (node (ref "Q13") (pin "S") (pinfunction "S_S") (pintype "passive"))
      (node (ref "Q14") (pin "S") (pinfunction "S_S") (pintype "passive"))
      (node (ref "Q15") (pin "S") (pinfunction "S_S") (pintype "passive"))
      (node (ref "Q16") (pin "S") (pinfunction "S_S") (pintype "passive"))
      (node (ref "Q17") (pin "S") (pinfunction "S_S") (pintype "passive"))
      (node (ref "Q18") (pin "S") (pinfunction "S_S") (pintype "passive"))
      (node (ref "Q19") (pin "S") (pinfunction "S_S") (pintype "passive"))
      (node (ref "Q2") (pin "S") (pinfunction "S_S") (pintype "passive"))
      (node (ref "Q20") (pin "S") (pinfunction "S_S") (pintype "passive"))
      (node (ref "Q21") (pin "S") (pinfunction "S_S") (pintype "passive"))
      (node (ref "Q22") (pin "S") (pinfunction "S_S") (pintype "passive"))
      (node (ref "Q23") (pin "S") (pinfunction "S_S") (pintype "passive"))
      (node (ref "Q24") (pin "S") (pinfunction "S_S") (pintype "passive"))
      (node (ref "Q25") (pin "S") (pinfunction "S_S") (pintype "passive"))
      (node (ref "Q26") (pin "S") (pinfunction "S_S") (pintype "passive"))
      (node (ref "Q27") (pin "S") (pinfunction "S_S") (pintype "passive"))
      (node (ref "Q28") (pin "S") (pinfunction "S_S") (pintype "passive"))
      (node (ref "Q29") (pin "S") (pinfunction "S_S") (pintype "passive"))
      (node (ref "Q3") (pin "S") (pinfunction "S_S") (pintype "passive"))
      (node (ref "Q30") (pin "S") (pinfunction "S_S") (pintype "passive"))
      (node (ref "Q31") (pin "S") (pinfunction "S_S") (pintype "passive"))
      (node (ref "Q32") (pin "S") (pinfunction "S_S") (pintype "passive"))
      (node (ref "Q33") (pin "S") (pinfunction "S_S") (pintype "passive"))
      (node (ref "Q34") (pin "S") (pinfunction "S_S") (pintype "passive"))
      (node (ref "Q35") (pin "S") (pinfunction "S_S") (pintype "passive"))
      (node (ref "Q36") (pin "S") (pinfunction "S_S") (pintype "passive"))
      (node (ref "Q37") (pin "S") (pinfunction "S_S") (pintype "passive"))
      (node (ref "Q38") (pin "S") (pinfunction "S_S") (pintype "passive"))
      (node (ref "Q39") (pin "S") (pinfunction "S_S") (pintype "passive"))
      (node (ref "Q4") (pin "S") (pinfunction "S_S") (pintype "passive"))
      (node (ref "Q40") (pin "S") (pinfunction "S_S") (pintype "passive"))
      (node (ref "Q41") (pin "S") (pinfunction "S_S") (pintype "passive"))
      (node (ref "Q42") (pin "S") (pinfunction "S_S") (pintype "passive"))
      (node (ref "Q43") (pin "S") (pinfunction "S_S") (pintype "passive"))
      (node (ref "Q44") (pin "S") (pinfunction "S_S") (pintype "passive"))
      (node (ref "Q45") (pin "S") (pinfunction "S_S") (pintype "passive"))
      (node (ref "Q46") (pin "S") (pinfunction "S_S") (pintype "passive"))
      (node (ref "Q47") (pin "S") (pinfunction "S_S") (pintype "passive"))
      (node (ref "Q48") (pin "S") (pinfunction "S_S") (pintype "passive"))
      (node (ref "Q5") (pin "S") (pinfunction "S_S") (pintype "passive"))
      (node (ref "Q6") (pin "S") (pinfunction "S_S") (pintype "passive"))
      (node (ref "Q7") (pin "S") (pinfunction "S_S") (pintype "passive"))
      (node (ref "Q8") (pin "S") (pinfunction "S_S") (pintype "passive"))
      (node (ref "Q9") (pin "S") (pinfunction "S_S") (pintype "passive"))
    )
    (net (code "54") (name "IN0") (class "Default")
      (node (ref "J1") (pin "2") (pinfunction "2_2") (pintype "bidirectional"))
      (node (ref "Q1") (pin "G") (pinfunction "G_G") (pintype "passive"))
    )
    (net (code "55") (name "IN1") (class "Default")
      (node (ref "J1") (pin "3") (pinfunction "3_3") (pintype "bidirectional"))
      (node (ref "Q2") (pin "G") (pinfunction "G_G") (pintype "passive"))
    )
    (net (code "56") (name "IN2") (class "Default")
      (node (ref "J1") (pin "4") (pinfunction "4_4") (pintype "bidirectional"))
      (node (ref "Q3") (pin "G") (pinfunction "G_G") (pintype "passive"))
    )
    (net (code "57") (name "IN3") (class "Default")
      (node (ref "J1") (pin "5") (pinfunction "5_5") (pintype "bidirectional"))
      (node (ref "Q4") (pin "G") (pinfunction "G_G") (pintype "passive"))
    )
    (net (code "58") (name "IN4") (class "Default")
      (node (ref "J1") (pin "6") (pinfunction "6_6") (pintype "bidirectional"))
      (node (ref "Q5") (pin "G") (pinfunction "G_G") (pintype "passive"))
    )
    (net (code "59") (name "IN5") (class "Default")
      (node (ref "J1") (pin "7") (pinfunction "7_7") (pintype "bidirectional"))
      (node (ref "Q6") (pin "G") (pinfunction "G_G") (pintype "passive"))
    )
    (net (code "60") (name "IN6") (class "Default")
      (node (ref "J1") (pin "8") (pinfunction "8_8") (pintype "bidirectional"))
      (node (ref "Q7") (pin "G") (pinfunction "G_G") (pintype "passive"))
    )
    (net (code "61") (name "IN7") (class "Default")
      (node (ref "J1") (pin "9") (pinfunction "9_9") (pintype "bidirectional"))
      (node (ref "Q8") (pin "G") (pinfunction "G_G") (pintype "passive"))
    )
    (net (code "62") (name "IN8") (class "Default")
      (node (ref "J1") (pin "12") (pinfunction "12_12") (pintype "bidirectional"))
      (node (ref "Q9") (pin "G") (pinfunction "G_G") (pintype "passive"))
    )
    (net (code "63") (name "IN9") (class "Default")
      (node (ref "J1") (pin "13") (pinfunction "13_13") (pintype "bidirectional"))
      (node (ref "Q10") (pin "G") (pinfunction "G_G") (pintype "passive"))
    )
    (net (code "64") (name "IN10") (class "Default")
      (node (ref "J1") (pin "14") (pinfunction "14_14") (pintype "bidirectional"))
      (node (ref "Q11") (pin "G") (pinfunction "G_G") (pintype "passive"))
    )
    (net (code "65") (name "IN11") (class "Default")
      (node (ref "J1") (pin "15") (pinfunction "15_15") (pintype "bidirectional"))
      (node (ref "Q12") (pin "G") (pinfunction "G_G") (pintype "passive"))
    )
    (net (code "66") (name "IN12") (class "Default")
      (node (ref "J1") (pin "16") (pinfunction "16_16") (pintype "bidirectional"))
      (node (ref "Q13") (pin "G") (pinfunction "G_G") (pintype "passive"))
    )
    (net (code "67") (name "IN13") (class "Default")
      (node (ref "J1") (pin "17") (pinfunction "17_17") (pintype "bidirectional"))
      (node (ref "Q14") (pin "G") (pinfunction "G_G") (pintype "passive"))
    )
    (net (code "68") (name "IN14") (class "Default")
      (node (ref "J1") (pin "18") (pinfunction "18_18") (pintype "bidirectional"))
      (node (ref "Q15") (pin "G") (pinfunction "G_G") (pintype "passive"))
    )
    (net (code "69") (name "IN15") (class "Default")
      (node (ref "J1") (pin "19") (pinfunction "19_19") (pintype "bidirectional"))
      (node (ref "Q16") (pin "G") (pinfunction "G_G") (pintype "passive"))
    )
  )
)
